# rev17.net
KiCad netlist of a schematic drawn in EAGLE
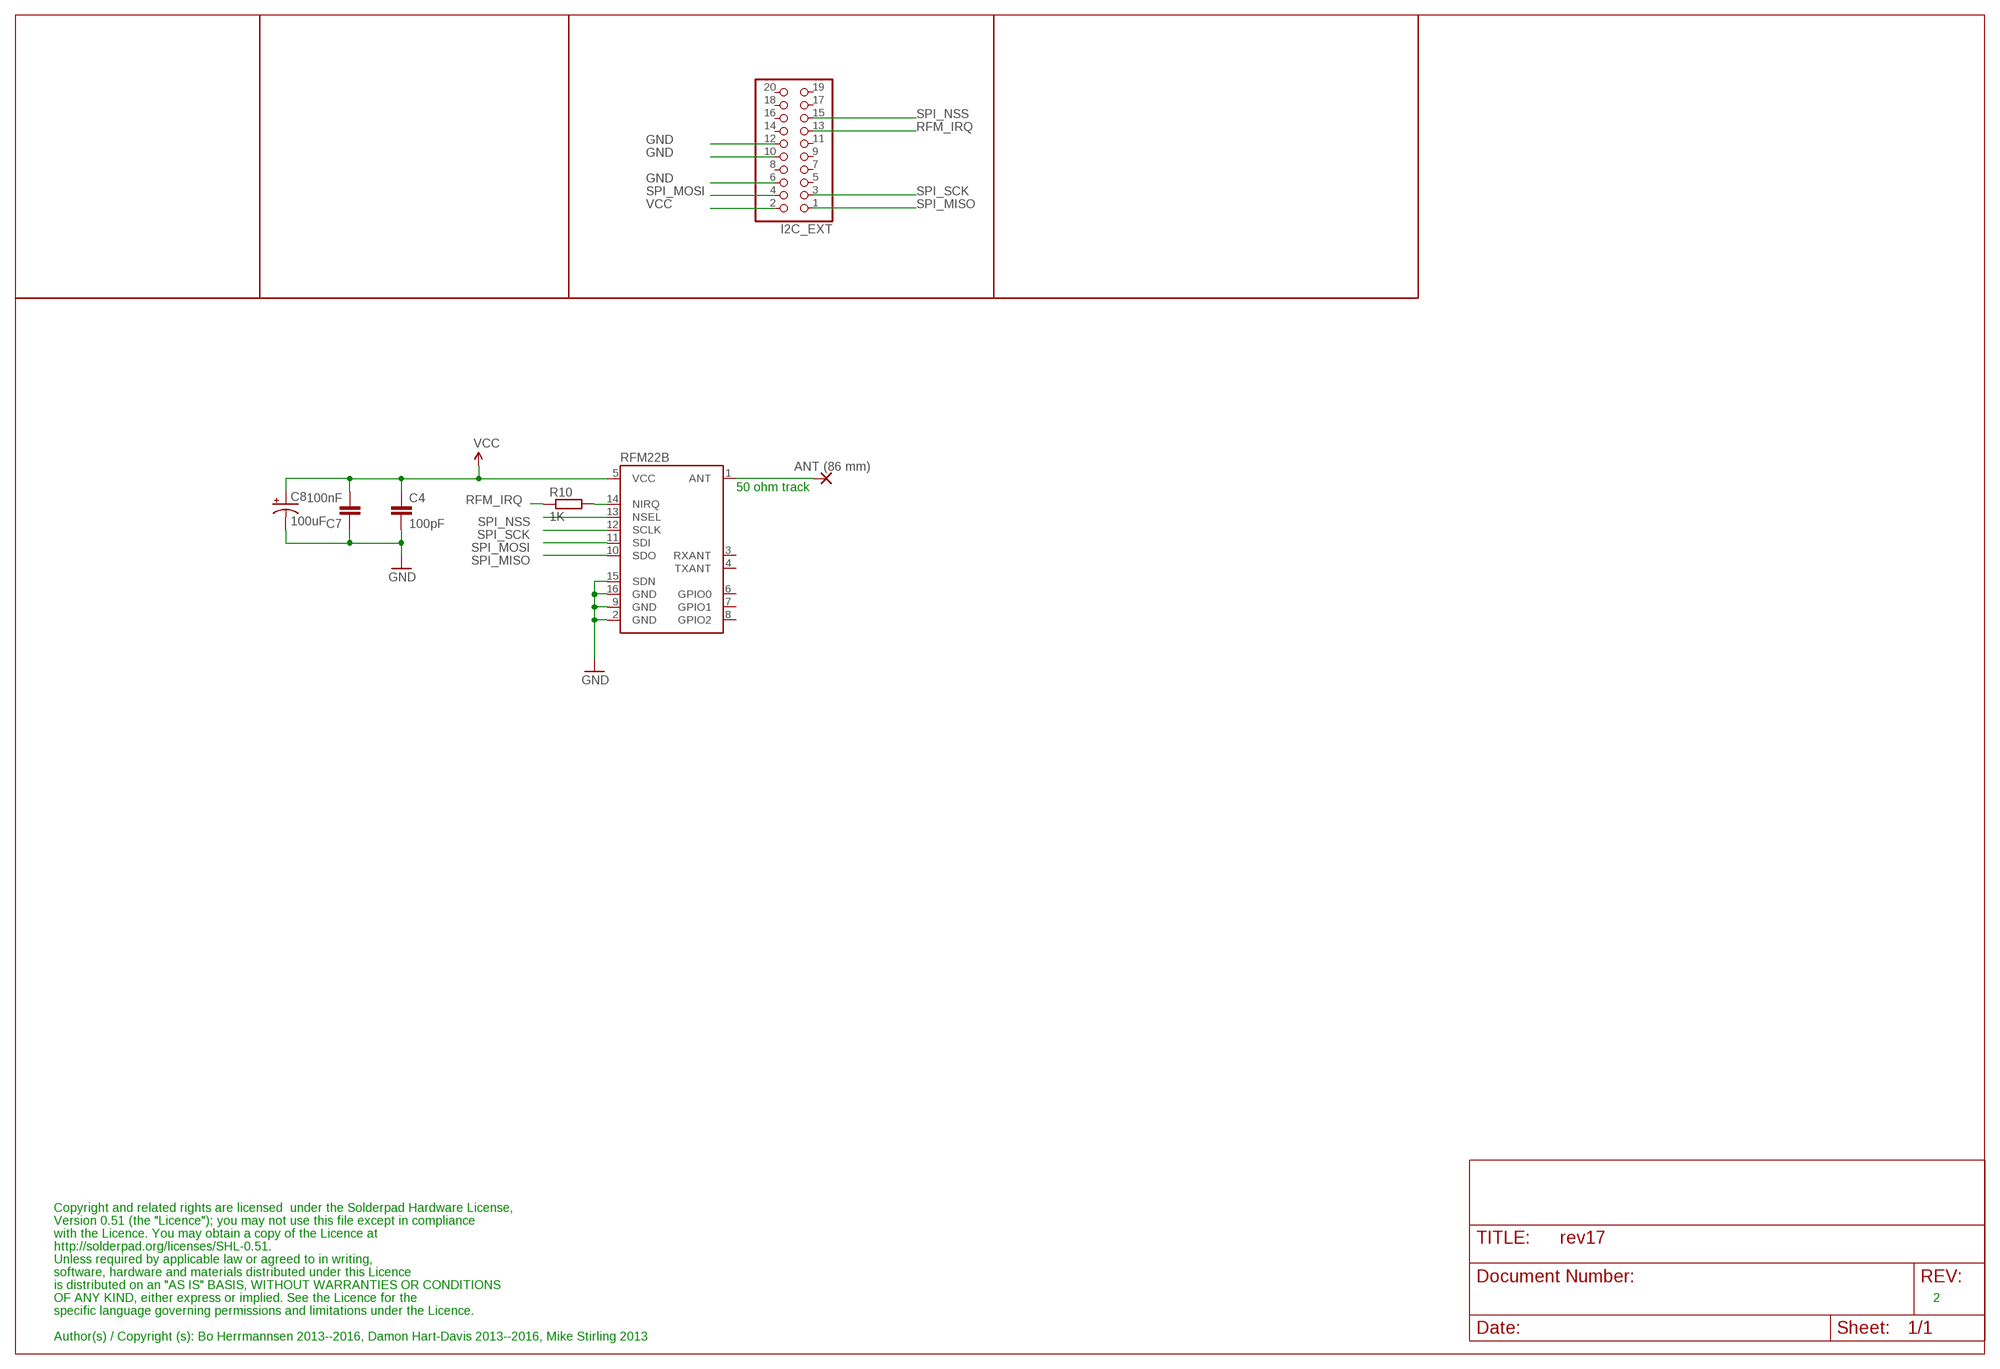
[diagram p0: schematic, sheet 1]

(export (version "E")
  (design (tool "Eeschema 10.0.6"))
  (components
    (comp (ref "ANT")
      (value "ANT (86 mm)")
      (footprint "eagle-import:2,15_1,0")
      (libsource (lib "eagle-import") (part "2,15/1,0"))
    )
    (comp (ref "C4")
      (value "100pF")
      (footprint "eagle-import:0603-CAP")
      (libsource (lib "eagle-import") (part "CAP0603-CAP"))
    )
    (comp (ref "C7")
      (value "100nF")
      (footprint "eagle-import:0603-CAP")
      (libsource (lib "eagle-import") (part "CAP0603-CAP"))
    )
    (comp (ref "C8")
      (value "100uF")
      (footprint "eagle-import:EIA3216")
      (libsource (lib "eagle-import") (part "CAP_POL1206"))
    )
    (comp (ref "I2C_EXT")
      (value "PINHD-2X10")
      (footprint "eagle-import:2X10")
      (libsource (lib "eagle-import") (part "PINHD-2X10"))
    )
    (comp (ref "R10")
      (value "1K")
      (footprint "eagle-import:R0603")
      (libsource (lib "eagle-import") (part "R-EU_R0603"))
    )
    (comp (ref "RFM22B")
      (value "RFM22SMD")
      (footprint "eagle-import:RFM22-XXX-S2")
      (libsource (lib "eagle-import") (part "RFM22SMD"))
    )
  )
  (nets
    (net (code "1") (name "/RFM_IRQ") (class "Default")
      (node (ref "I2C_EXT") (pin "13") (pinfunction "13_13") (pintype "passive"))
      (node (ref "R10") (pin "1") (pinfunction "1_1") (pintype "passive"))
    )
    (net (code "2") (name "/SPI_MISO") (class "Default")
      (node (ref "I2C_EXT") (pin "1") (pinfunction "1_1") (pintype "passive"))
      (node (ref "RFM22B") (pin "10") (pinfunction "SDO_10") (pintype "output"))
    )
    (net (code "3") (name "/SPI_MOSI") (class "Default")
      (node (ref "I2C_EXT") (pin "4") (pinfunction "4_4") (pintype "passive"))
      (node (ref "RFM22B") (pin "11") (pinfunction "SDI_11") (pintype "input"))
    )
    (net (code "4") (name "/SPI_NSS") (class "Default")
      (node (ref "I2C_EXT") (pin "15") (pinfunction "15_15") (pintype "passive"))
      (node (ref "RFM22B") (pin "13") (pinfunction "NSEL_13") (pintype "input"))
    )
    (net (code "5") (name "/SPI_SCK") (class "Default")
      (node (ref "I2C_EXT") (pin "3") (pinfunction "3_3") (pintype "passive"))
      (node (ref "RFM22B") (pin "12") (pinfunction "SCLK_12") (pintype "input"))
    )
    (net (code "6") (name "GND") (class "Default")
      (node (ref "C4") (pin "2") (pinfunction "2_2") (pintype "passive"))
      (node (ref "C7") (pin "1") (pinfunction "1_1") (pintype "passive"))
      (node (ref "C8") (pin "C") (pinfunction "-_C") (pintype "passive"))
      (node (ref "I2C_EXT") (pin "10") (pinfunction "10_10") (pintype "passive"))
      (node (ref "I2C_EXT") (pin "12") (pinfunction "12_12") (pintype "passive"))
      (node (ref "I2C_EXT") (pin "6") (pinfunction "6_6") (pintype "passive"))
      (node (ref "RFM22B") (pin "15") (pinfunction "SDN_15") (pintype "input"))
      (node (ref "RFM22B") (pin "16") (pinfunction "GND_16") (pintype "power_in"))
      (node (ref "RFM22B") (pin "2") (pinfunction "GND_2") (pintype "power_in"))
      (node (ref "RFM22B") (pin "9") (pinfunction "GND_9") (pintype "power_in"))
    )
    (net (code "7") (name "Net-(ANT-P)") (class "Default")
      (node (ref "ANT") (pin "1") (pinfunction "P_1") (pintype "passive"))
      (node (ref "RFM22B") (pin "1") (pinfunction "ANT_1") (pintype "bidirectional"))
    )
    (net (code "8") (name "Net-(RFM22B-NIRQ)") (class "Default")
      (node (ref "R10") (pin "2") (pinfunction "2_2") (pintype "passive"))
      (node (ref "RFM22B") (pin "14") (pinfunction "NIRQ_14") (pintype "output"))
    )
    (net (code "9") (name "VCC") (class "Default")
      (node (ref "C4") (pin "1") (pinfunction "1_1") (pintype "passive"))
      (node (ref "C7") (pin "2") (pinfunction "2_2") (pintype "passive"))
      (node (ref "C8") (pin "A") (pinfunction "+_A") (pintype "passive"))
      (node (ref "I2C_EXT") (pin "2") (pinfunction "2_2") (pintype "passive"))
      (node (ref "RFM22B") (pin "5") (pinfunction "VCC_5") (pintype "bidirectional"))
    )
    (net (code "10") (name "unconnected-(I2C_EXT-Pad5)") (class "Default")
      (node (ref "I2C_EXT") (pin "5") (pinfunction "5_5") (pintype "passive"))
    )
    (net (code "11") (name "unconnected-(I2C_EXT-Pad7)") (class "Default")
      (node (ref "I2C_EXT") (pin "7") (pinfunction "7_7") (pintype "passive"))
    )
    (net (code "12") (name "unconnected-(I2C_EXT-Pad8)") (class "Default")
      (node (ref "I2C_EXT") (pin "8") (pinfunction "8_8") (pintype "passive"))
    )
    (net (code "13") (name "unconnected-(I2C_EXT-Pad9)") (class "Default")
      (node (ref "I2C_EXT") (pin "9") (pinfunction "9_9") (pintype "passive"))
    )
    (net (code "14") (name "unconnected-(I2C_EXT-Pad11)") (class "Default")
      (node (ref "I2C_EXT") (pin "11") (pinfunction "11_11") (pintype "passive"))
    )
    (net (code "15") (name "unconnected-(I2C_EXT-Pad14)") (class "Default")
      (node (ref "I2C_EXT") (pin "14") (pinfunction "14_14") (pintype "passive"))
    )
    (net (code "16") (name "unconnected-(I2C_EXT-Pad16)") (class "Default")
      (node (ref "I2C_EXT") (pin "16") (pinfunction "16_16") (pintype "passive"))
    )
    (net (code "17") (name "unconnected-(I2C_EXT-Pad17)") (class "Default")
      (node (ref "I2C_EXT") (pin "17") (pinfunction "17_17") (pintype "passive"))
    )
    (net (code "18") (name "unconnected-(I2C_EXT-Pad18)") (class "Default")
      (node (ref "I2C_EXT") (pin "18") (pinfunction "18_18") (pintype "passive"))
    )
    (net (code "19") (name "unconnected-(I2C_EXT-Pad19)") (class "Default")
      (node (ref "I2C_EXT") (pin "19") (pinfunction "19_19") (pintype "passive"))
    )
    (net (code "20") (name "unconnected-(I2C_EXT-Pad20)") (class "Default")
      (node (ref "I2C_EXT") (pin "20") (pinfunction "20_20") (pintype "passive"))
    )
    (net (code "21") (name "unconnected-(RFM22B-GPIO0-Pad6)") (class "Default")
      (node (ref "RFM22B") (pin "6") (pinfunction "GPIO0_6") (pintype "bidirectional"))
    )
    (net (code "22") (name "unconnected-(RFM22B-GPIO1-Pad7)") (class "Default")
      (node (ref "RFM22B") (pin "7") (pinfunction "GPIO1_7") (pintype "bidirectional"))
    )
    (net (code "23") (name "unconnected-(RFM22B-GPIO2-Pad8)") (class "Default")
      (node (ref "RFM22B") (pin "8") (pinfunction "GPIO2_8") (pintype "bidirectional"))
    )
    (net (code "24") (name "unconnected-(RFM22B-RXANT-Pad3)") (class "Default")
      (node (ref "RFM22B") (pin "3") (pinfunction "RXANT_3") (pintype "input"))
    )
    (net (code "25") (name "unconnected-(RFM22B-TXANT-Pad4)") (class "Default")
      (node (ref "RFM22B") (pin "4") (pinfunction "TXANT_4") (pintype "input"))
    )
  )
)
